# Memory_SCH.net
KiCad netlist of a schematic drawn in Altium Designer
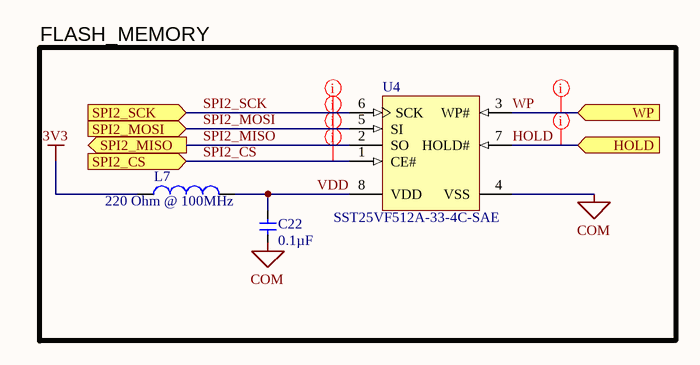
[diagram p0: Memory_SCH.SchDoc]

(export (version "E")
  (design (tool "Eeschema 10.0.6"))
  (components
    (comp (ref "C22")
      (value "GRM188R71C104KA01D")
      (footprint "C0603")
      (description "CAP CER 0.1UF 16V 10% X7R 0603")
      (fields (field (name "TOLERANCE") "±10%") (field (name "CAPACITANCE") "0.1µF"))
      (libsource (lib "Rockets_2015-2016") (part "GRM188R71C104KA01D"))
    )
    (comp (ref "L7")
      (value "BLM21PG221SN1D")
      (footprint "L0805")
      (description "FERRITE CHIP 220 OHM 0805")
      (fields (field (name "IMPEDANCE @ FREQUENCY") "220 Ohm @ 100MHz"))
      (libsource (lib "Rockets_2015-2016") (part "BLM21PG221SN1D"))
    )
    (comp (ref "U4")
      (value "SST25VF512A-33-4C-SAE")
      (footprint "MCHP-SOIC-SA8_N")
      (description "512 Kbit SPI Serial Flash, 2.7 to 3.6 V, 33 MHz, 0 to 70 degC, 8-pin SOIC (SA8), Tube")
      (fields (field (name "MANUFACTURER") "Microchip"))
      (libsource (lib "Altium Content Vault") (part "MCHP-SST25VFXXX-SOIC-8"))
    )
  )
  (nets
    (net (code "1") (name "/HOLD") (class "Default")
      (node (ref "U4") (pin "7") (pinfunction "HOLD#_7") (pintype "input"))
    )
    (net (code "2") (name "/SPI2_CS") (class "Default")
      (node (ref "U4") (pin "1") (pinfunction "CE#_1") (pintype "input"))
    )
    (net (code "3") (name "/SPI2_MISO") (class "Default")
      (node (ref "U4") (pin "2") (pinfunction "SO_2") (pintype "tri_state"))
    )
    (net (code "4") (name "/SPI2_MOSI") (class "Default")
      (node (ref "U4") (pin "5") (pinfunction "SI_5") (pintype "input"))
    )
    (net (code "5") (name "/SPI2_SCK") (class "Default")
      (node (ref "U4") (pin "6") (pinfunction "SCK_6") (pintype "input"))
    )
    (net (code "6") (name "/VDD") (class "Default")
      (node (ref "C22") (pin "1") (pinfunction "1_1") (pintype "passive"))
      (node (ref "L7") (pin "2") (pinfunction "2_2") (pintype "passive"))
      (node (ref "U4") (pin "8") (pinfunction "VDD_8") (pintype "power_in"))
    )
    (net (code "7") (name "/WP") (class "Default")
      (node (ref "U4") (pin "3") (pinfunction "WP#_3") (pintype "input"))
    )
    (net (code "8") (name "3V3") (class "Default")
      (node (ref "L7") (pin "1") (pinfunction "1_1") (pintype "passive"))
    )
    (net (code "9") (name "COM") (class "Default")
      (node (ref "C22") (pin "2") (pinfunction "2_2") (pintype "passive"))
      (node (ref "U4") (pin "4") (pinfunction "VSS_4") (pintype "power_in"))
    )
  )
)
